# LCD.net
KiCad netlist of a schematic drawn in Altium Designer
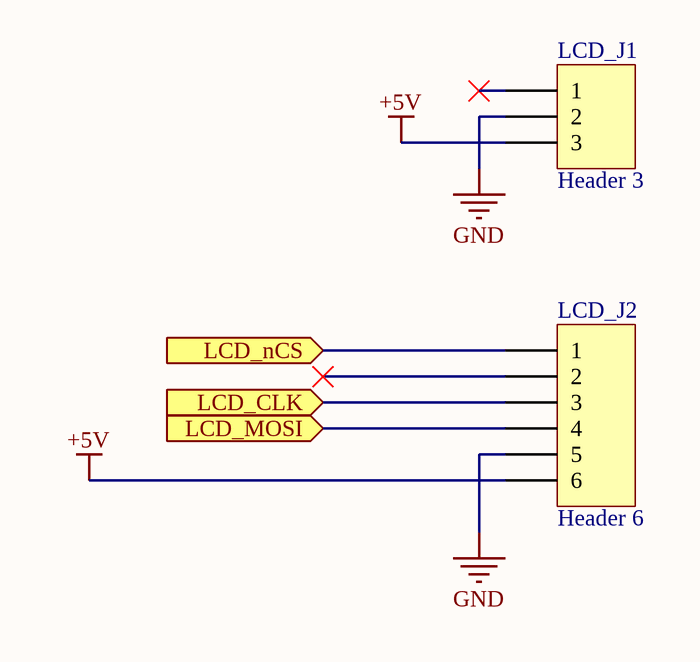
[diagram p0: LCD.SchDoc]

(export (version "E")
  (design (tool "Eeschema 10.0.6"))
  (components
    (comp (ref "LCD_J1")
      (value "Header 3")
      (footprint "HDR1X3")
      (description "Header, 3-Pin")
      (fields (field (name "PUBLISHER") "Altium Limited"))
      (libsource (lib "Miscellaneous Connectors") (part "Header 3"))
    )
    (comp (ref "LCD_J2")
      (value "Header 6")
      (footprint "HDR1X6")
      (description "Header, 6-Pin")
      (fields (field (name "PUBLISHER") "Altium Limited"))
      (libsource (lib "Miscellaneous Connectors") (part "Header 6"))
    )
  )
  (nets
    (net (code "1") (name "+5V") (class "Default")
      (node (ref "LCD_J1") (pin "3") (pinfunction "3_3") (pintype "passive"))
      (node (ref "LCD_J2") (pin "6") (pinfunction "6_6") (pintype "passive"))
    )
    (net (code "2") (name "/LCD_CLK") (class "Default")
      (node (ref "LCD_J2") (pin "3") (pinfunction "3_3") (pintype "passive"))
    )
    (net (code "3") (name "/LCD_MOSI") (class "Default")
      (node (ref "LCD_J2") (pin "4") (pinfunction "4_4") (pintype "passive"))
    )
    (net (code "4") (name "/LCD_nCS") (class "Default")
      (node (ref "LCD_J2") (pin "1") (pinfunction "1_1") (pintype "passive"))
    )
    (net (code "5") (name "GND") (class "Default")
      (node (ref "LCD_J1") (pin "2") (pinfunction "2_2") (pintype "passive"))
      (node (ref "LCD_J2") (pin "5") (pinfunction "5_5") (pintype "passive"))
    )
    (net (code "6") (name "unconnected-(LCD_J1-Pad1)") (class "Default")
      (node (ref "LCD_J1") (pin "1") (pinfunction "1_1") (pintype "passive+no_connect"))
    )
    (net (code "7") (name "unconnected-(LCD_J2-Pad2)") (class "Default")
      (node (ref "LCD_J2") (pin "2") (pinfunction "2_2") (pintype "passive+no_connect"))
    )
  )
)
